# PQS42019_5_v1.net
KiCad netlist of a schematic drawn in EAGLE
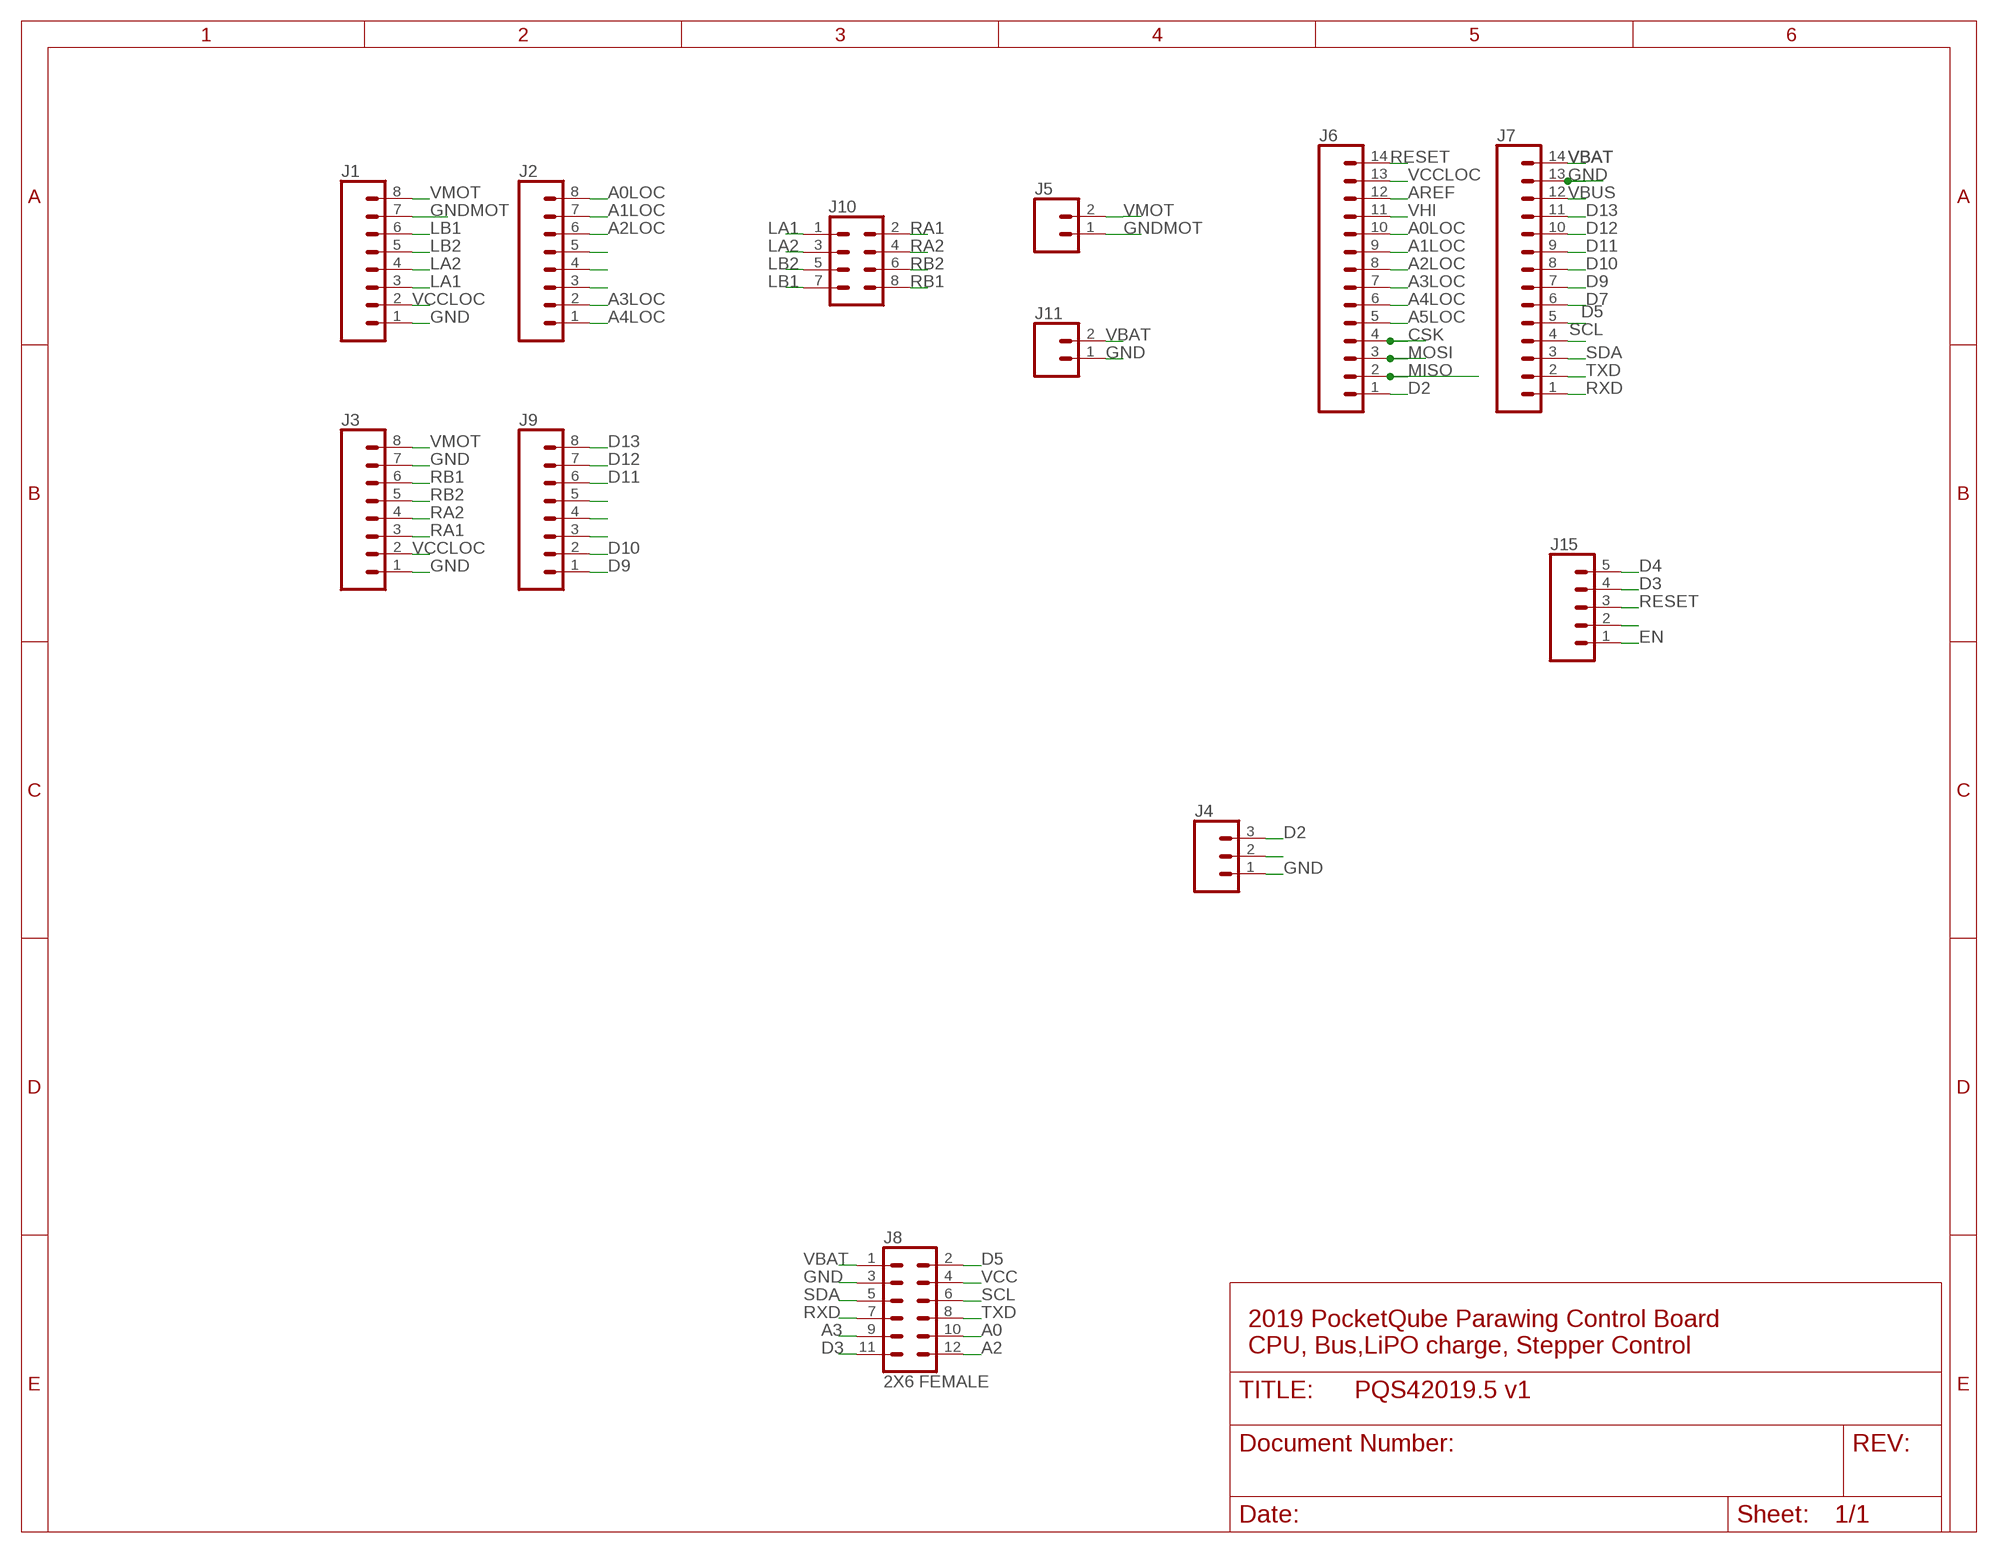
[diagram p0: schematic, sheet 1]

(export (version "E")
  (design (tool "Eeschema 10.0.6"))
  (components
    (comp (ref "J1")
      (value "CONN_08\"")
      (footprint "eagle-import:1X08")
      (libsource (lib "eagle-import") (part "CONN_08{dblquote}"))
    )
    (comp (ref "J2")
      (value "CONN_08\"")
      (footprint "eagle-import:1X08")
      (libsource (lib "eagle-import") (part "CONN_08{dblquote}"))
    )
    (comp (ref "J3")
      (value "CONN_08\"")
      (footprint "eagle-import:1X08")
      (libsource (lib "eagle-import") (part "CONN_08{dblquote}"))
    )
    (comp (ref "J4")
      (value "CONN_03")
      (footprint "eagle-import:1X03")
      (libsource (lib "eagle-import") (part "CONN_03"))
    )
    (comp (ref "J5")
      (value "CONN_02")
      (footprint "eagle-import:1X02")
      (libsource (lib "eagle-import") (part "CONN_02"))
    )
    (comp (ref "J6")
      (value "CONN_14")
      (footprint "eagle-import:1X14")
      (libsource (lib "eagle-import") (part "CONN_14"))
    )
    (comp (ref "J7")
      (value "CONN_14")
      (footprint "eagle-import:1X14")
      (libsource (lib "eagle-import") (part "CONN_14"))
    )
    (comp (ref "J8")
      (value "2X6 FEMALE")
      (footprint "eagle-import:2X6")
      (libsource (lib "eagle-import") (part "CONN_06X2PTH_FEMALE"))
    )
    (comp (ref "J9")
      (value "CONN_08\"")
      (footprint "eagle-import:1X08")
      (libsource (lib "eagle-import") (part "CONN_08{dblquote}"))
    )
    (comp (ref "J10")
      (value "CONN_04X2")
      (footprint "eagle-import:2X4")
      (libsource (lib "eagle-import") (part "CONN_04X2"))
    )
    (comp (ref "J11")
      (value "CONN_02")
      (footprint "eagle-import:1X02")
      (libsource (lib "eagle-import") (part "CONN_02"))
    )
    (comp (ref "J15")
      (value "CONN_05")
      (footprint "eagle-import:1X05")
      (libsource (lib "eagle-import") (part "CONN_05"))
    )
  )
  (nets
    (net (code "1") (name "/A0") (class "Default")
      (node (ref "J8") (pin "10") (pinfunction "10_10") (pintype "passive"))
    )
    (net (code "2") (name "/A0LOC") (class "Default")
      (node (ref "J2") (pin "8") (pinfunction "8_8") (pintype "passive"))
      (node (ref "J6") (pin "10") (pinfunction "10_10") (pintype "passive"))
    )
    (net (code "3") (name "/A1LOC") (class "Default")
      (node (ref "J2") (pin "7") (pinfunction "7_7") (pintype "passive"))
      (node (ref "J6") (pin "9") (pinfunction "9_9") (pintype "passive"))
    )
    (net (code "4") (name "/A2") (class "Default")
      (node (ref "J8") (pin "12") (pinfunction "12_12") (pintype "passive"))
    )
    (net (code "5") (name "/A2LOC") (class "Default")
      (node (ref "J2") (pin "6") (pinfunction "6_6") (pintype "passive"))
      (node (ref "J6") (pin "8") (pinfunction "8_8") (pintype "passive"))
    )
    (net (code "6") (name "/A3") (class "Default")
      (node (ref "J8") (pin "9") (pinfunction "9_9") (pintype "passive"))
    )
    (net (code "7") (name "/A3LOC") (class "Default")
      (node (ref "J2") (pin "2") (pinfunction "2_2") (pintype "passive"))
      (node (ref "J6") (pin "7") (pinfunction "7_7") (pintype "passive"))
    )
    (net (code "8") (name "/A4LOC") (class "Default")
      (node (ref "J2") (pin "1") (pinfunction "1_1") (pintype "passive"))
      (node (ref "J6") (pin "6") (pinfunction "6_6") (pintype "passive"))
    )
    (net (code "9") (name "/A5LOC") (class "Default")
      (node (ref "J6") (pin "5") (pinfunction "5_5") (pintype "passive"))
    )
    (net (code "10") (name "/AREF") (class "Default")
      (node (ref "J6") (pin "12") (pinfunction "12_12") (pintype "passive"))
    )
    (net (code "11") (name "/CSK") (class "Default")
      (node (ref "J6") (pin "4") (pinfunction "4_4") (pintype "passive"))
    )
    (net (code "12") (name "/D2") (class "Default")
      (node (ref "J4") (pin "3") (pinfunction "3_3") (pintype "passive"))
      (node (ref "J6") (pin "1") (pinfunction "1_1") (pintype "passive"))
    )
    (net (code "13") (name "/D3") (class "Default")
      (node (ref "J15") (pin "4") (pinfunction "4_4") (pintype "passive"))
      (node (ref "J8") (pin "11") (pinfunction "11_11") (pintype "passive"))
    )
    (net (code "14") (name "/D4") (class "Default")
      (node (ref "J15") (pin "5") (pinfunction "5_5") (pintype "passive"))
    )
    (net (code "15") (name "/D5") (class "Default")
      (node (ref "J7") (pin "5") (pinfunction "5_5") (pintype "passive"))
      (node (ref "J8") (pin "2") (pinfunction "2_2") (pintype "passive"))
    )
    (net (code "16") (name "/D7") (class "Default")
      (node (ref "J7") (pin "6") (pinfunction "6_6") (pintype "passive"))
    )
    (net (code "17") (name "/D9") (class "Default")
      (node (ref "J7") (pin "7") (pinfunction "7_7") (pintype "passive"))
      (node (ref "J9") (pin "1") (pinfunction "1_1") (pintype "passive"))
    )
    (net (code "18") (name "/D10") (class "Default")
      (node (ref "J7") (pin "8") (pinfunction "8_8") (pintype "passive"))
      (node (ref "J9") (pin "2") (pinfunction "2_2") (pintype "passive"))
    )
    (net (code "19") (name "/D11") (class "Default")
      (node (ref "J7") (pin "9") (pinfunction "9_9") (pintype "passive"))
      (node (ref "J9") (pin "6") (pinfunction "6_6") (pintype "passive"))
    )
    (net (code "20") (name "/D12") (class "Default")
      (node (ref "J7") (pin "10") (pinfunction "10_10") (pintype "passive"))
      (node (ref "J9") (pin "7") (pinfunction "7_7") (pintype "passive"))
    )
    (net (code "21") (name "/D13") (class "Default")
      (node (ref "J7") (pin "11") (pinfunction "11_11") (pintype "passive"))
      (node (ref "J9") (pin "8") (pinfunction "8_8") (pintype "passive"))
    )
    (net (code "22") (name "/EN") (class "Default")
      (node (ref "J15") (pin "1") (pinfunction "1_1") (pintype "passive"))
    )
    (net (code "23") (name "/GND") (class "Default")
      (node (ref "J1") (pin "1") (pinfunction "1_1") (pintype "passive"))
      (node (ref "J11") (pin "1") (pinfunction "1_1") (pintype "passive"))
      (node (ref "J3") (pin "1") (pinfunction "1_1") (pintype "passive"))
      (node (ref "J3") (pin "7") (pinfunction "7_7") (pintype "passive"))
      (node (ref "J4") (pin "1") (pinfunction "1_1") (pintype "passive"))
      (node (ref "J7") (pin "13") (pinfunction "13_13") (pintype "passive"))
      (node (ref "J8") (pin "3") (pinfunction "3_3") (pintype "passive"))
    )
    (net (code "24") (name "/GNDMOT") (class "Default")
      (node (ref "J1") (pin "7") (pinfunction "7_7") (pintype "passive"))
      (node (ref "J5") (pin "1") (pinfunction "1_1") (pintype "passive"))
    )
    (net (code "25") (name "/LA1") (class "Default")
      (node (ref "J1") (pin "3") (pinfunction "3_3") (pintype "passive"))
      (node (ref "J10") (pin "1") (pinfunction "1_1") (pintype "passive"))
    )
    (net (code "26") (name "/LA2") (class "Default")
      (node (ref "J1") (pin "4") (pinfunction "4_4") (pintype "passive"))
      (node (ref "J10") (pin "3") (pinfunction "3_3") (pintype "passive"))
    )
    (net (code "27") (name "/LB1") (class "Default")
      (node (ref "J1") (pin "6") (pinfunction "6_6") (pintype "passive"))
      (node (ref "J10") (pin "7") (pinfunction "7_7") (pintype "passive"))
    )
    (net (code "28") (name "/LB2") (class "Default")
      (node (ref "J1") (pin "5") (pinfunction "5_5") (pintype "passive"))
      (node (ref "J10") (pin "5") (pinfunction "5_5") (pintype "passive"))
    )
    (net (code "29") (name "/MISO") (class "Default")
      (node (ref "J6") (pin "2") (pinfunction "2_2") (pintype "passive"))
    )
    (net (code "30") (name "/MOSI") (class "Default")
      (node (ref "J6") (pin "3") (pinfunction "3_3") (pintype "passive"))
    )
    (net (code "31") (name "/RA1") (class "Default")
      (node (ref "J10") (pin "2") (pinfunction "2_2") (pintype "passive"))
      (node (ref "J3") (pin "3") (pinfunction "3_3") (pintype "passive"))
    )
    (net (code "32") (name "/RA2") (class "Default")
      (node (ref "J10") (pin "4") (pinfunction "4_4") (pintype "passive"))
      (node (ref "J3") (pin "4") (pinfunction "4_4") (pintype "passive"))
    )
    (net (code "33") (name "/RB1") (class "Default")
      (node (ref "J10") (pin "8") (pinfunction "8_8") (pintype "passive"))
      (node (ref "J3") (pin "6") (pinfunction "6_6") (pintype "passive"))
    )
    (net (code "34") (name "/RB2") (class "Default")
      (node (ref "J10") (pin "6") (pinfunction "6_6") (pintype "passive"))
      (node (ref "J3") (pin "5") (pinfunction "5_5") (pintype "passive"))
    )
    (net (code "35") (name "/RESET") (class "Default")
      (node (ref "J15") (pin "3") (pinfunction "3_3") (pintype "passive"))
      (node (ref "J6") (pin "14") (pinfunction "14_14") (pintype "passive"))
    )
    (net (code "36") (name "/RXD") (class "Default")
      (node (ref "J7") (pin "1") (pinfunction "1_1") (pintype "passive"))
      (node (ref "J8") (pin "7") (pinfunction "7_7") (pintype "passive"))
    )
    (net (code "37") (name "/SCL") (class "Default")
      (node (ref "J7") (pin "4") (pinfunction "4_4") (pintype "passive"))
      (node (ref "J8") (pin "6") (pinfunction "6_6") (pintype "passive"))
    )
    (net (code "38") (name "/SDA") (class "Default")
      (node (ref "J7") (pin "3") (pinfunction "3_3") (pintype "passive"))
      (node (ref "J8") (pin "5") (pinfunction "5_5") (pintype "passive"))
    )
    (net (code "39") (name "/TXD") (class "Default")
      (node (ref "J7") (pin "2") (pinfunction "2_2") (pintype "passive"))
      (node (ref "J8") (pin "8") (pinfunction "8_8") (pintype "passive"))
    )
    (net (code "40") (name "/VBAT") (class "Default")
      (node (ref "J11") (pin "2") (pinfunction "2_2") (pintype "passive"))
      (node (ref "J7") (pin "14") (pinfunction "14_14") (pintype "passive"))
      (node (ref "J8") (pin "1") (pinfunction "1_1") (pintype "passive"))
    )
    (net (code "41") (name "/VBUS") (class "Default")
      (node (ref "J7") (pin "12") (pinfunction "12_12") (pintype "passive"))
    )
    (net (code "42") (name "/VCC") (class "Default")
      (node (ref "J8") (pin "4") (pinfunction "4_4") (pintype "passive"))
    )
    (net (code "43") (name "/VCCLOC") (class "Default")
      (node (ref "J1") (pin "2") (pinfunction "2_2") (pintype "passive"))
      (node (ref "J3") (pin "2") (pinfunction "2_2") (pintype "passive"))
      (node (ref "J6") (pin "13") (pinfunction "13_13") (pintype "passive"))
    )
    (net (code "44") (name "/VHI") (class "Default")
      (node (ref "J6") (pin "11") (pinfunction "11_11") (pintype "passive"))
    )
    (net (code "45") (name "/VMOT") (class "Default")
      (node (ref "J1") (pin "8") (pinfunction "8_8") (pintype "passive"))
      (node (ref "J3") (pin "8") (pinfunction "8_8") (pintype "passive"))
      (node (ref "J5") (pin "2") (pinfunction "2_2") (pintype "passive"))
    )
    (net (code "46") (name "unconnected-(J2-Pad3)") (class "Default")
      (node (ref "J2") (pin "3") (pinfunction "3_3") (pintype "passive"))
    )
    (net (code "47") (name "unconnected-(J2-Pad4)") (class "Default")
      (node (ref "J2") (pin "4") (pinfunction "4_4") (pintype "passive"))
    )
    (net (code "48") (name "unconnected-(J2-Pad5)") (class "Default")
      (node (ref "J2") (pin "5") (pinfunction "5_5") (pintype "passive"))
    )
    (net (code "49") (name "unconnected-(J4-Pad2)") (class "Default")
      (node (ref "J4") (pin "2") (pinfunction "2_2") (pintype "passive"))
    )
    (net (code "50") (name "unconnected-(J9-Pad3)") (class "Default")
      (node (ref "J9") (pin "3") (pinfunction "3_3") (pintype "passive"))
    )
    (net (code "51") (name "unconnected-(J9-Pad4)") (class "Default")
      (node (ref "J9") (pin "4") (pinfunction "4_4") (pintype "passive"))
    )
    (net (code "52") (name "unconnected-(J9-Pad5)") (class "Default")
      (node (ref "J9") (pin "5") (pinfunction "5_5") (pintype "passive"))
    )
    (net (code "53") (name "unconnected-(J15-Pad2)") (class "Default")
      (node (ref "J15") (pin "2") (pinfunction "2_2") (pintype "passive"))
    )
  )
)
